# Sensor_de_Nivel_Ultra-Sonido.net
KiCad netlist of a schematic drawn in EAGLE
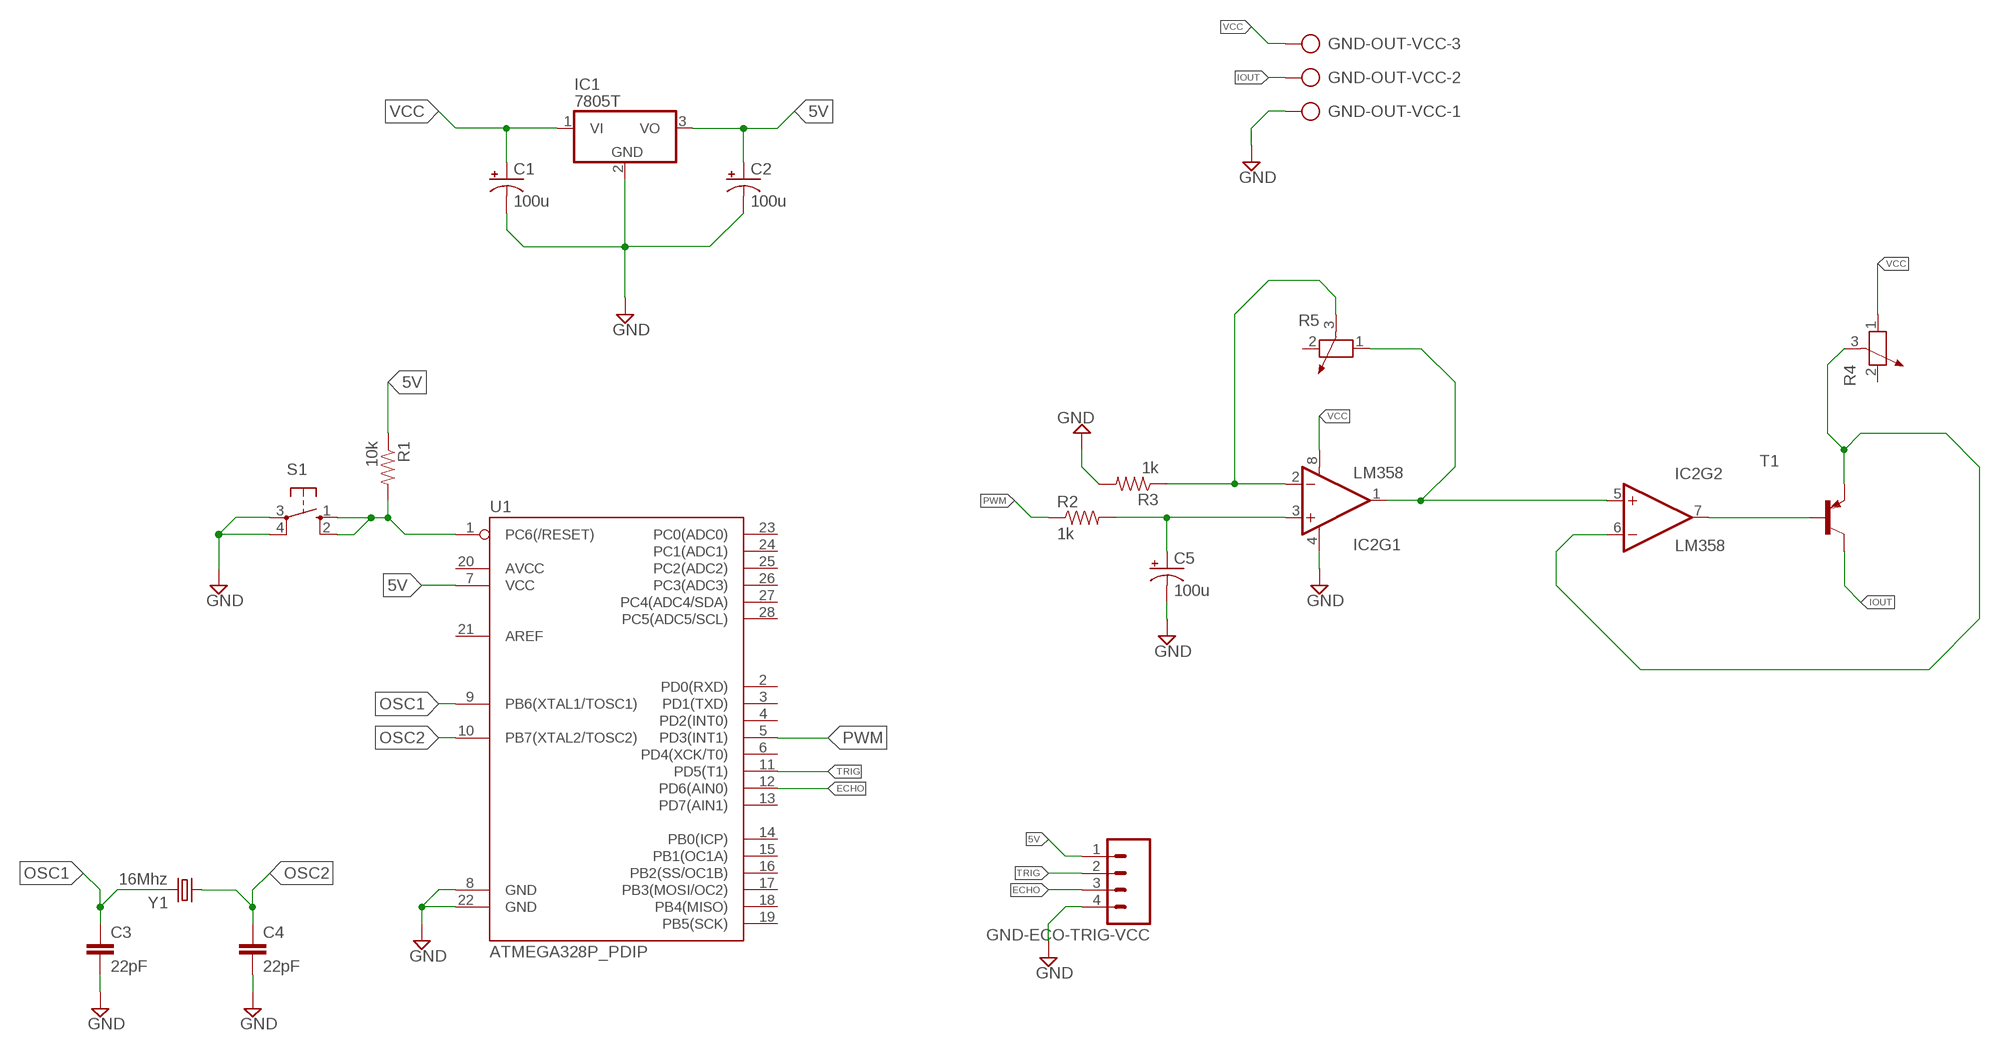
[diagram p0: schematic, sheet 1]

(export (version "E")
  (design (tool "Eeschema 10.0.6"))
  (components
    (comp (ref "C1")
      (value "100u")
      (footprint "eagle-import:CPOL-RADIAL-10UF-25V-KIT")
      (libsource (lib "eagle-import") (part "10UF-25V-20%(PTH)KIT"))
    )
    (comp (ref "C2")
      (value "100u")
      (footprint "eagle-import:CPOL-RADIAL-10UF-25V-KIT")
      (libsource (lib "eagle-import") (part "10UF-25V-20%(PTH)KIT"))
    )
    (comp (ref "C3")
      (value "22pF")
      (footprint "eagle-import:CAP-PTH-SMALL-KIT")
      (libsource (lib "eagle-import") (part "0.1UF-50V-20%(PTH)KIT-EZ"))
    )
    (comp (ref "C4")
      (value "22pF")
      (footprint "eagle-import:CAP-PTH-SMALL-KIT")
      (libsource (lib "eagle-import") (part "0.1UF-50V-20%(PTH)KIT-EZ"))
    )
    (comp (ref "C5")
      (value "100u")
      (footprint "eagle-import:CPOL-RADIAL-10UF-25V-KIT")
      (libsource (lib "eagle-import") (part "10UF-25V-20%(PTH)KIT"))
    )
    (comp (ref "GND-ECO-TRIG-VCC")
      (value "M04LONGPADS")
      (footprint "eagle-import:1X04_LONGPADS")
      (libsource (lib "eagle-import") (part "M04LONGPADS"))
    )
    (comp (ref "GND-OUT-VCC")
      (value "AK500/3")
      (footprint "eagle-import:AK500_3")
      (libsource (lib "eagle-import") (part "AK500/3"))
    )
    (comp (ref "IC1")
      (value "7805T")
      (footprint "eagle-import:TO220H")
      (libsource (lib "eagle-import") (part "78T05"))
    )
    (comp (ref "IC2")
      (value "LM358")
      (footprint "eagle-import:DIP08")
      (libsource (lib "eagle-import") (part "LM358"))
    )
    (comp (ref "R1")
      (value "10k")
      (footprint "eagle-import:AXIAL-0.3-KIT")
      (libsource (lib "eagle-import") (part "RESISTORKIT"))
    )
    (comp (ref "R2")
      (value "1k")
      (footprint "eagle-import:AXIAL-0.3-KIT")
      (libsource (lib "eagle-import") (part "RESISTORKIT"))
    )
    (comp (ref "R3")
      (value "1k")
      (footprint "eagle-import:AXIAL-0.3-KIT")
      (libsource (lib "eagle-import") (part "RESISTORKIT"))
    )
    (comp (ref "R4")
      (value "POTENTIOMETER_PT_SPIN")
      (footprint "eagle-import:PT-SPIN")
      (libsource (lib "eagle-import") (part "POTENTIOMETER_PT_SPIN"))
    )
    (comp (ref "R5")
      (value "POTENTIOMETER_PT_SPIN")
      (footprint "eagle-import:PT-SPIN")
      (libsource (lib "eagle-import") (part "POTENTIOMETER_PT_SPIN"))
    )
    (comp (ref "S1")
      (value "10-XX")
      (footprint "eagle-import:B3F-10XX")
      (fields (field (name "MPN") "B3F-1000"))
      (libsource (lib "eagle-import") (part "10-XX"))
    )
    (comp (ref "T1")
      (value "BC558A-PNP-TO92-EBC")
      (footprint "eagle-import:TO92-EBC")
      (libsource (lib "eagle-import") (part "-PNP-TO92-EBCBC558A"))
    )
    (comp (ref "U1")
      (value "ATMEGA328P_PDIP")
      (footprint "eagle-import:DIL28-3")
      (libsource (lib "eagle-import") (part "ATMEGA328P_PDIP"))
    )
    (comp (ref "Y1")
      (value "16Mhz")
      (footprint "eagle-import:HC49US")
      (libsource (lib "eagle-import") (part "CRYSTALHC49US"))
    )
  )
  (nets
    (net (code "1") (name "5V") (class "Default")
      (node (ref "C2") (pin "1") (pinfunction "+_1") (pintype "passive"))
      (node (ref "GND-ECO-TRIG-VCC") (pin "1") (pinfunction "1_1") (pintype "passive"))
      (node (ref "IC1") (pin "3") (pinfunction "VO_3") (pintype "passive"))
      (node (ref "R1") (pin "P$1") (pinfunction "1_P$1") (pintype "passive"))
      (node (ref "U1") (pin "7") (pinfunction "VCC_7") (pintype "bidirectional"))
    )
    (net (code "2") (name "ECHO") (class "Default")
      (node (ref "GND-ECO-TRIG-VCC") (pin "3") (pinfunction "3_3") (pintype "passive"))
      (node (ref "U1") (pin "12") (pinfunction "PD6(AIN0)_12") (pintype "bidirectional"))
    )
    (net (code "3") (name "GND") (class "Default")
      (node (ref "C1") (pin "2") (pinfunction "-_2") (pintype "passive"))
      (node (ref "C2") (pin "2") (pinfunction "-_2") (pintype "passive"))
      (node (ref "C3") (pin "2") (pinfunction "2_2") (pintype "passive"))
      (node (ref "C4") (pin "2") (pinfunction "2_2") (pintype "passive"))
      (node (ref "C5") (pin "2") (pinfunction "-_2") (pintype "passive"))
      (node (ref "GND-ECO-TRIG-VCC") (pin "4") (pinfunction "4_4") (pintype "passive"))
      (node (ref "GND-OUT-VCC") (pin "1") (pinfunction "KL_1") (pintype "passive"))
      (node (ref "IC1") (pin "2") (pinfunction "GND_2") (pintype "passive"))
      (node (ref "IC2") (pin "4") (pinfunction "V-_4") (pintype "power_in"))
      (node (ref "R3") (pin "P$2") (pinfunction "2_P$2") (pintype "passive"))
      (node (ref "S1") (pin "3") (pinfunction "P_3") (pintype "passive"))
      (node (ref "S1") (pin "4") (pinfunction "P1_4") (pintype "passive"))
      (node (ref "U1") (pin "22") (pinfunction "GND_22") (pintype "bidirectional"))
      (node (ref "U1") (pin "8") (pinfunction "GND_8") (pintype "bidirectional"))
    )
    (net (code "4") (name "IOUT") (class "Default")
      (node (ref "GND-OUT-VCC") (pin "2") (pinfunction "KL_2") (pintype "passive"))
      (node (ref "T1") (pin "C") (pinfunction "C_C") (pintype "passive"))
    )
    (net (code "5") (name "Net-(C5-+)") (class "Default")
      (node (ref "C5") (pin "1") (pinfunction "+_1") (pintype "passive"))
      (node (ref "IC2") (pin "3") (pinfunction "+IN_3") (pintype "input"))
      (node (ref "R2") (pin "P$2") (pinfunction "2_P$2") (pintype "passive"))
    )
    (net (code "6") (name "Net-(IC2A--IN)") (class "Default")
      (node (ref "IC2") (pin "2") (pinfunction "-IN_2") (pintype "input"))
      (node (ref "R3") (pin "P$1") (pinfunction "1_P$1") (pintype "passive"))
      (node (ref "R5") (pin "3") (pinfunction "3_3") (pintype "passive"))
    )
    (net (code "7") (name "Net-(IC2A-OUT)") (class "Default")
      (node (ref "IC2") (pin "1") (pinfunction "OUT_1") (pintype "output"))
      (node (ref "IC2") (pin "5") (pinfunction "+IN_5") (pintype "input"))
      (node (ref "R5") (pin "1") (pinfunction "1_1") (pintype "passive"))
    )
    (net (code "8") (name "Net-(IC2B--IN)") (class "Default")
      (node (ref "IC2") (pin "6") (pinfunction "-IN_6") (pintype "input"))
      (node (ref "R4") (pin "3") (pinfunction "3_3") (pintype "passive"))
      (node (ref "T1") (pin "E") (pinfunction "E_E") (pintype "passive"))
    )
    (net (code "9") (name "Net-(IC2B-OUT)") (class "Default")
      (node (ref "IC2") (pin "7") (pinfunction "OUT_7") (pintype "output"))
      (node (ref "T1") (pin "B") (pinfunction "B_B") (pintype "passive"))
    )
    (net (code "10") (name "Net-(R1-2)") (class "Default")
      (node (ref "R1") (pin "P$2") (pinfunction "2_P$2") (pintype "passive"))
      (node (ref "S1") (pin "1") (pinfunction "S_1") (pintype "passive"))
      (node (ref "S1") (pin "2") (pinfunction "S1_2") (pintype "passive"))
      (node (ref "U1") (pin "1") (pinfunction "PC6(/RESET)_1") (pintype "bidirectional"))
    )
    (net (code "11") (name "OSC1") (class "Default")
      (node (ref "C3") (pin "1") (pinfunction "1_1") (pintype "passive"))
      (node (ref "U1") (pin "9") (pinfunction "PB6(XTAL1/TOSC1)_9") (pintype "bidirectional"))
      (node (ref "Y1") (pin "2") (pinfunction "2_2") (pintype "passive"))
    )
    (net (code "12") (name "OSC2") (class "Default")
      (node (ref "C4") (pin "1") (pinfunction "1_1") (pintype "passive"))
      (node (ref "U1") (pin "10") (pinfunction "PB7(XTAL2/TOSC2)_10") (pintype "bidirectional"))
      (node (ref "Y1") (pin "1") (pinfunction "1_1") (pintype "passive"))
    )
    (net (code "13") (name "PWM") (class "Default")
      (node (ref "R2") (pin "P$1") (pinfunction "1_P$1") (pintype "passive"))
      (node (ref "U1") (pin "5") (pinfunction "PD3(INT1)_5") (pintype "bidirectional"))
    )
    (net (code "14") (name "TRIG") (class "Default")
      (node (ref "GND-ECO-TRIG-VCC") (pin "2") (pinfunction "2_2") (pintype "passive"))
      (node (ref "U1") (pin "11") (pinfunction "PD5(T1)_11") (pintype "bidirectional"))
    )
    (net (code "15") (name "VCC") (class "Default")
      (node (ref "C1") (pin "1") (pinfunction "+_1") (pintype "passive"))
      (node (ref "GND-OUT-VCC") (pin "3") (pinfunction "KL_3") (pintype "passive"))
      (node (ref "IC1") (pin "1") (pinfunction "VI_1") (pintype "input"))
      (node (ref "IC2") (pin "8") (pinfunction "V+_8") (pintype "power_in"))
      (node (ref "R4") (pin "1") (pinfunction "1_1") (pintype "passive"))
    )
    (net (code "16") (name "unconnected-(R4-Pad2)") (class "Default")
      (node (ref "R4") (pin "2") (pinfunction "2_2") (pintype "passive"))
    )
    (net (code "17") (name "unconnected-(R5-Pad2)") (class "Default")
      (node (ref "R5") (pin "2") (pinfunction "2_2") (pintype "passive"))
    )
    (net (code "18") (name "unconnected-(U1-AREF-Pad21)") (class "Default")
      (node (ref "U1") (pin "21") (pinfunction "AREF_21") (pintype "bidirectional"))
    )
    (net (code "19") (name "unconnected-(U1-AVCC-Pad20)") (class "Default")
      (node (ref "U1") (pin "20") (pinfunction "AVCC_20") (pintype "bidirectional"))
    )
    (net (code "20") (name "unconnected-(U1-PB0(ICP)-Pad14)") (class "Default")
      (node (ref "U1") (pin "14") (pinfunction "PB0(ICP)_14") (pintype "bidirectional"))
    )
    (net (code "21") (name "unconnected-(U1-PB1(OC1A)-Pad15)") (class "Default")
      (node (ref "U1") (pin "15") (pinfunction "PB1(OC1A)_15") (pintype "bidirectional"))
    )
    (net (code "22") (name "unconnected-(U1-PB2(SS{slash}OC1B)-Pad16)") (class "Default")
      (node (ref "U1") (pin "16") (pinfunction "PB2(SS/OC1B)_16") (pintype "bidirectional"))
    )
    (net (code "23") (name "unconnected-(U1-PB3(MOSI{slash}OC2)-Pad17)") (class "Default")
      (node (ref "U1") (pin "17") (pinfunction "PB3(MOSI/OC2)_17") (pintype "bidirectional"))
    )
    (net (code "24") (name "unconnected-(U1-PB4(MISO)-Pad18)") (class "Default")
      (node (ref "U1") (pin "18") (pinfunction "PB4(MISO)_18") (pintype "bidirectional"))
    )
    (net (code "25") (name "unconnected-(U1-PB5(SCK)-Pad19)") (class "Default")
      (node (ref "U1") (pin "19") (pinfunction "PB5(SCK)_19") (pintype "bidirectional"))
    )
    (net (code "26") (name "unconnected-(U1-PC0(ADC0)-Pad23)") (class "Default")
      (node (ref "U1") (pin "23") (pinfunction "PC0(ADC0)_23") (pintype "bidirectional"))
    )
    (net (code "27") (name "unconnected-(U1-PC1(ADC1)-Pad24)") (class "Default")
      (node (ref "U1") (pin "24") (pinfunction "PC1(ADC1)_24") (pintype "bidirectional"))
    )
    (net (code "28") (name "unconnected-(U1-PC2(ADC2)-Pad25)") (class "Default")
      (node (ref "U1") (pin "25") (pinfunction "PC2(ADC2)_25") (pintype "bidirectional"))
    )
    (net (code "29") (name "unconnected-(U1-PC3(ADC3)-Pad26)") (class "Default")
      (node (ref "U1") (pin "26") (pinfunction "PC3(ADC3)_26") (pintype "bidirectional"))
    )
    (net (code "30") (name "unconnected-(U1-PC4(ADC4{slash}SDA)-Pad27)") (class "Default")
      (node (ref "U1") (pin "27") (pinfunction "PC4(ADC4/SDA)_27") (pintype "bidirectional"))
    )
    (net (code "31") (name "unconnected-(U1-PC5(ADC5{slash}SCL)-Pad28)") (class "Default")
      (node (ref "U1") (pin "28") (pinfunction "PC5(ADC5/SCL)_28") (pintype "bidirectional"))
    )
    (net (code "32") (name "unconnected-(U1-PD0(RXD)-Pad2)") (class "Default")
      (node (ref "U1") (pin "2") (pinfunction "PD0(RXD)_2") (pintype "bidirectional"))
    )
    (net (code "33") (name "unconnected-(U1-PD1(TXD)-Pad3)") (class "Default")
      (node (ref "U1") (pin "3") (pinfunction "PD1(TXD)_3") (pintype "bidirectional"))
    )
    (net (code "34") (name "unconnected-(U1-PD2(INT0)-Pad4)") (class "Default")
      (node (ref "U1") (pin "4") (pinfunction "PD2(INT0)_4") (pintype "bidirectional"))
    )
    (net (code "35") (name "unconnected-(U1-PD4(XCK{slash}T0)-Pad6)") (class "Default")
      (node (ref "U1") (pin "6") (pinfunction "PD4(XCK/T0)_6") (pintype "bidirectional"))
    )
    (net (code "36") (name "unconnected-(U1-PD7(AIN1)-Pad13)") (class "Default")
      (node (ref "U1") (pin "13") (pinfunction "PD7(AIN1)_13") (pintype "bidirectional"))
    )
  )
)
